# PWR.net
KiCad netlist of a schematic drawn in Altium Designer
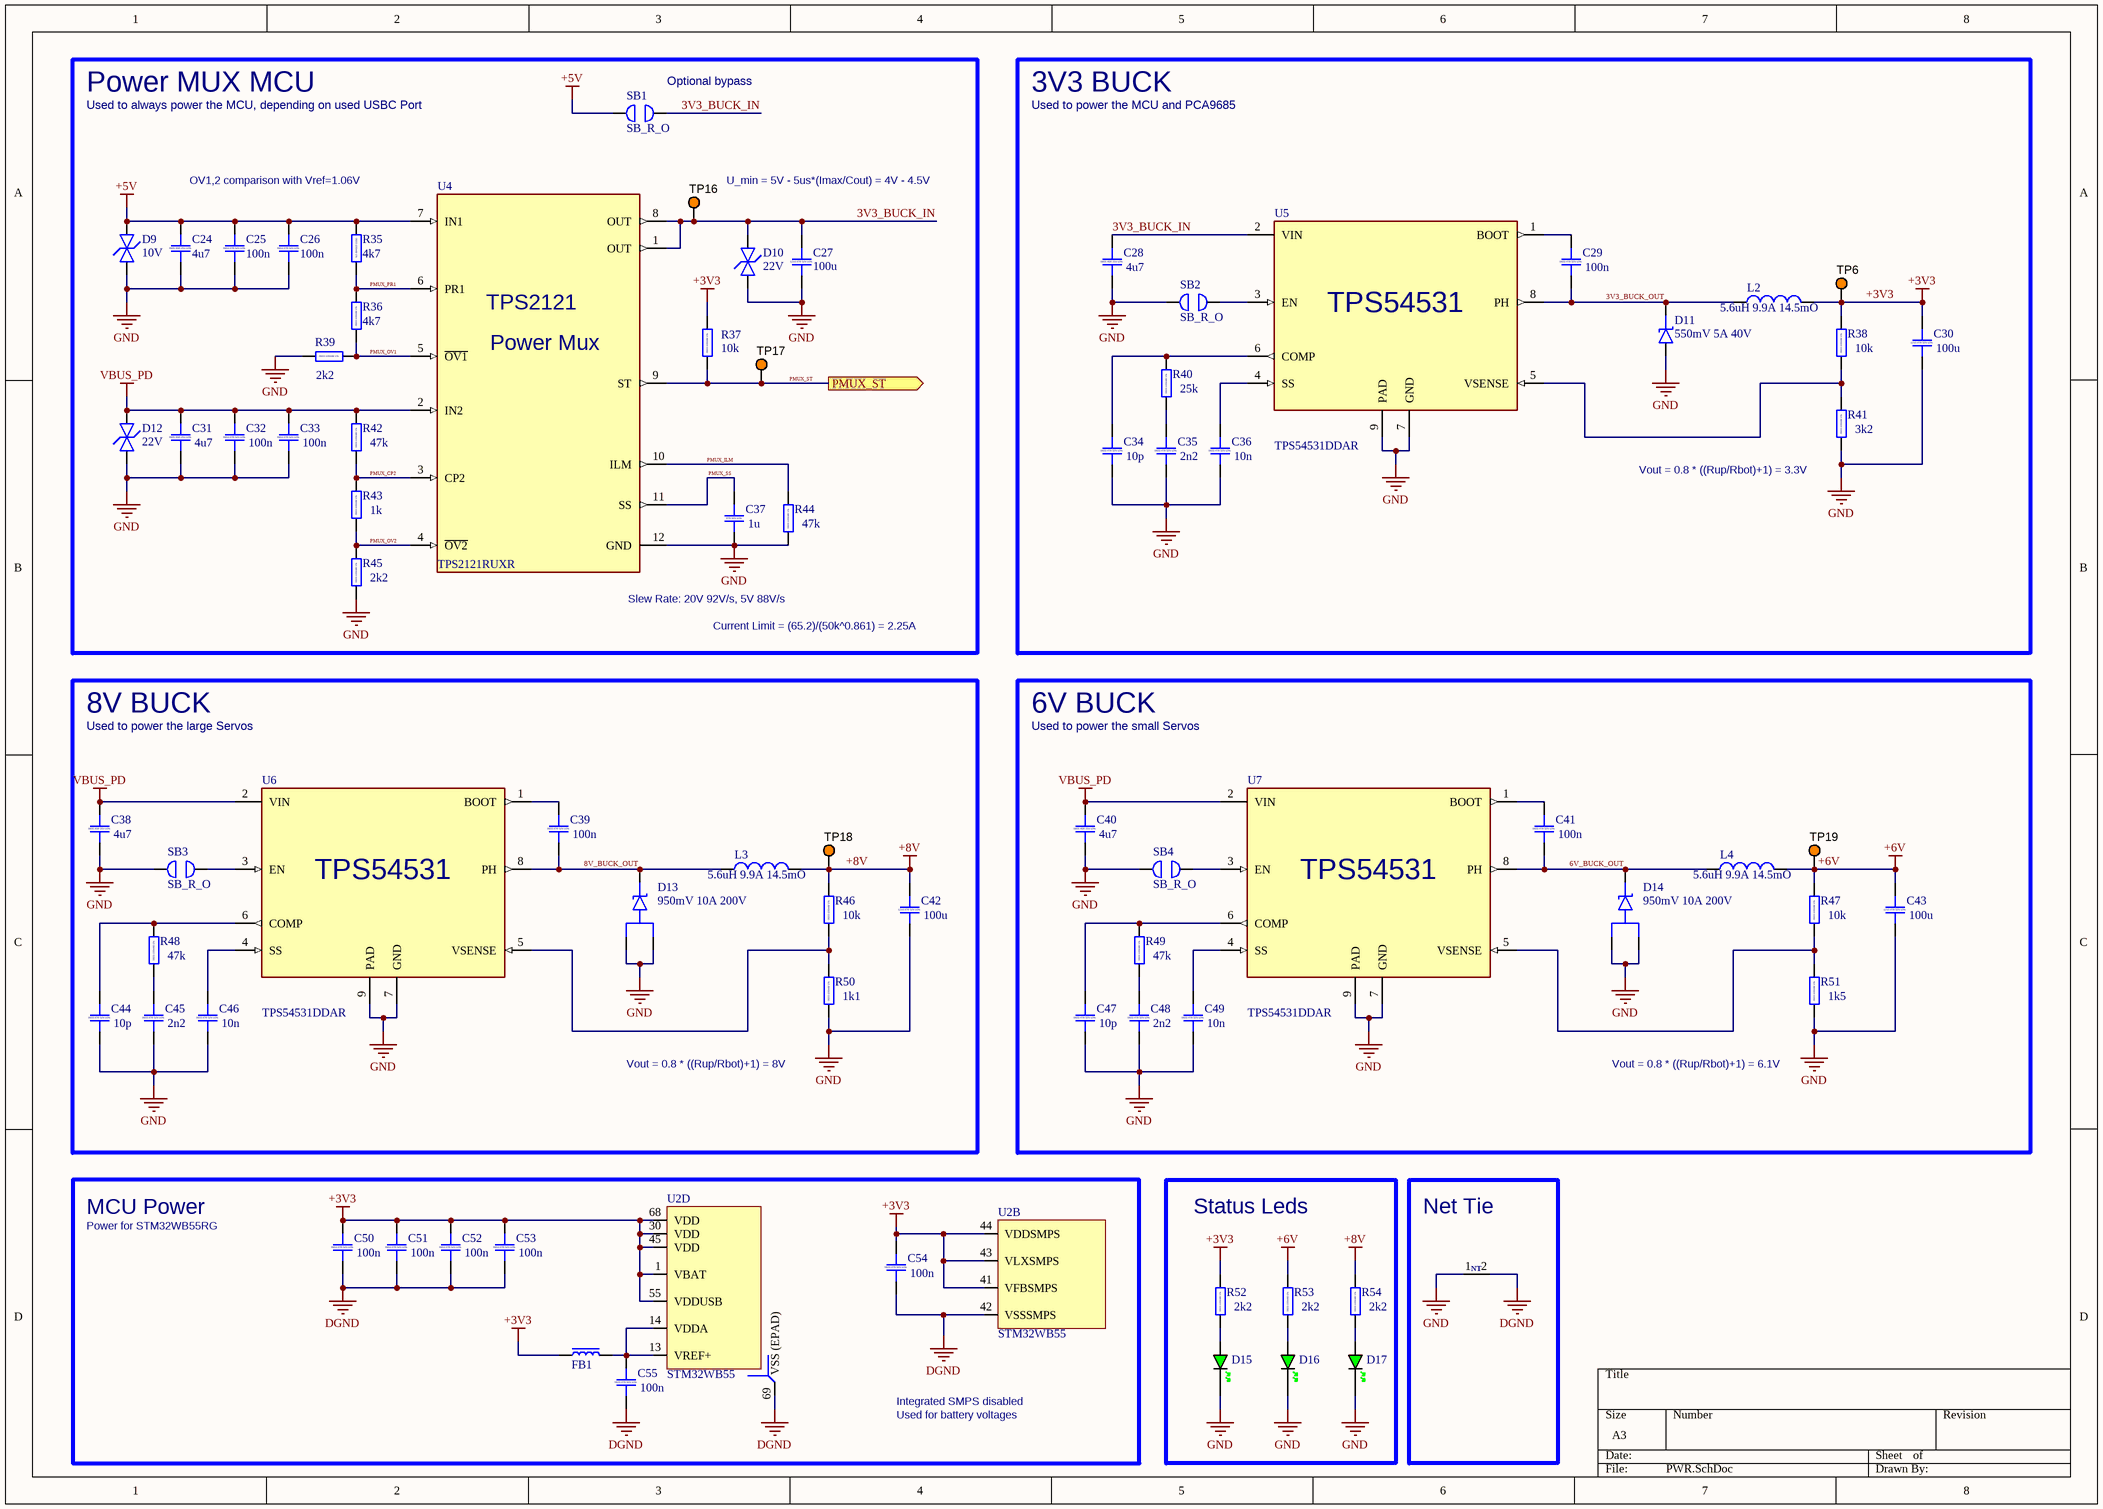
[diagram p0: PWR.SchDoc]

(export (version "E")
  (design (tool "Eeschema 10.0.6"))
  (components
    (comp (ref "C24")
      (value "4u7")
      (footprint "CAP_0805")
      (description "Capacitor SMD 0805")
      (fields (field (name "SOURCE") "Schematic-Lib-PhilsLab.SchLib"))
      (libsource (lib "") (part "CAP_EL_NP_5MM_2"))
    )
    (comp (ref "C25")
      (value "100n")
      (footprint "CAP_0603")
      (description "Capacitor SMD 0603")
      (fields (field (name "SOURCE") "Schematic-Lib-PhilsLab.SchLib"))
      (libsource (lib "Leonhard Waibl") (part "CAP_EL_NP_5MM"))
    )
    (comp (ref "C26")
      (value "100n")
      (footprint "CAP_0603")
      (description "Capacitor SMD 0603")
      (fields (field (name "SOURCE") "Schematic-Lib-PhilsLab.SchLib"))
      (libsource (lib "Leonhard Waibl") (part "CAP_EL_NP_5MM"))
    )
    (comp (ref "C27")
      (value "100u")
      (footprint "CAP_1210")
      (description "Capacitor SMD 1210")
      (fields (field (name "SOURCE") "Schematic-Lib-PhilsLab.SchLib"))
      (libsource (lib "") (part "CAP_EL_NP_5MM_1"))
    )
    (comp (ref "C28")
      (value "4u7")
      (footprint "CAP_0805")
      (description "Capacitor SMD 0805")
      (fields (field (name "SOURCE") "Schematic-Lib-PhilsLab.SchLib"))
      (libsource (lib "") (part "CAP_EL_NP_5MM_2"))
    )
    (comp (ref "C29")
      (value "100n")
      (footprint "CAP_0603")
      (description "Capacitor SMD 0603")
      (fields (field (name "SOURCE") "Schematic-Lib-PhilsLab.SchLib"))
      (libsource (lib "Leonhard Waibl") (part "CAP_EL_NP_5MM"))
    )
    (comp (ref "C30")
      (value "100u")
      (footprint "CAP_1210")
      (description "Capacitor SMD 1210")
      (fields (field (name "SOURCE") "Schematic-Lib-PhilsLab.SchLib"))
      (libsource (lib "") (part "CAP_EL_NP_5MM_1"))
    )
    (comp (ref "C31")
      (value "4u7")
      (footprint "CAP_0805")
      (description "Capacitor SMD 0805")
      (fields (field (name "SOURCE") "Schematic-Lib-PhilsLab.SchLib"))
      (libsource (lib "") (part "CAP_EL_NP_5MM_2"))
    )
    (comp (ref "C32")
      (value "100n")
      (footprint "CAP_0603")
      (description "Capacitor SMD 0603")
      (fields (field (name "SOURCE") "Schematic-Lib-PhilsLab.SchLib"))
      (libsource (lib "Leonhard Waibl") (part "CAP_EL_NP_5MM"))
    )
    (comp (ref "C33")
      (value "100n")
      (footprint "CAP_0603")
      (description "Capacitor SMD 0603")
      (fields (field (name "SOURCE") "Schematic-Lib-PhilsLab.SchLib"))
      (libsource (lib "Leonhard Waibl") (part "CAP_EL_NP_5MM"))
    )
    (comp (ref "C34")
      (value "10p")
      (footprint "CAP_0603")
      (description "Capacitor SMD 0603")
      (fields (field (name "SOURCE") "Schematic-Lib-PhilsLab.SchLib"))
      (libsource (lib "Leonhard Waibl") (part "CAP_EL_NP_5MM"))
    )
    (comp (ref "C35")
      (value "2n2")
      (footprint "CAP_0603")
      (description "Capacitor SMD 0603")
      (fields (field (name "SOURCE") "Schematic-Lib-PhilsLab.SchLib"))
      (libsource (lib "Leonhard Waibl") (part "CAP_EL_NP_5MM"))
    )
    (comp (ref "C36")
      (value "10n")
      (footprint "CAP_0603")
      (description "Capacitor SMD 0603")
      (fields (field (name "SOURCE") "Schematic-Lib-PhilsLab.SchLib"))
      (libsource (lib "Leonhard Waibl") (part "CAP_EL_NP_5MM"))
    )
    (comp (ref "C37")
      (value "1u")
      (footprint "CAP_0603")
      (description "Capacitor SMD 0603")
      (fields (field (name "SOURCE") "Schematic-Lib-PhilsLab.SchLib"))
      (libsource (lib "Leonhard Waibl") (part "CAP_EL_NP_5MM"))
    )
    (comp (ref "C38")
      (value "4u7")
      (footprint "CAP_0805")
      (description "Capacitor SMD 0805")
      (fields (field (name "SOURCE") "Schematic-Lib-PhilsLab.SchLib"))
      (libsource (lib "") (part "CAP_EL_NP_5MM_2"))
    )
    (comp (ref "C39")
      (value "100n")
      (footprint "CAP_0603")
      (description "Capacitor SMD 0603")
      (fields (field (name "SOURCE") "Schematic-Lib-PhilsLab.SchLib"))
      (libsource (lib "Leonhard Waibl") (part "CAP_EL_NP_5MM"))
    )
    (comp (ref "C40")
      (value "4u7")
      (footprint "CAP_0805")
      (description "Capacitor SMD 0805")
      (fields (field (name "SOURCE") "Schematic-Lib-PhilsLab.SchLib"))
      (libsource (lib "") (part "CAP_EL_NP_5MM_2"))
    )
    (comp (ref "C41")
      (value "100n")
      (footprint "CAP_0603")
      (description "Capacitor SMD 0603")
      (fields (field (name "SOURCE") "Schematic-Lib-PhilsLab.SchLib"))
      (libsource (lib "Leonhard Waibl") (part "CAP_EL_NP_5MM"))
    )
    (comp (ref "C42")
      (value "100u")
      (footprint "CAP_1210")
      (description "Capacitor SMD 1210")
      (fields (field (name "SOURCE") "Schematic-Lib-PhilsLab.SchLib"))
      (libsource (lib "") (part "CAP_EL_NP_5MM_1"))
    )
    (comp (ref "C43")
      (value "100u")
      (footprint "CAP_1210")
      (description "Capacitor SMD 1210")
      (fields (field (name "SOURCE") "Schematic-Lib-PhilsLab.SchLib"))
      (libsource (lib "") (part "CAP_EL_NP_5MM_1"))
    )
    (comp (ref "C44")
      (value "10p")
      (footprint "CAP_0603")
      (description "Capacitor SMD 0603")
      (fields (field (name "SOURCE") "Schematic-Lib-PhilsLab.SchLib"))
      (libsource (lib "Leonhard Waibl") (part "CAP_EL_NP_5MM"))
    )
    (comp (ref "C45")
      (value "2n2")
      (footprint "CAP_0603")
      (description "Capacitor SMD 0603")
      (fields (field (name "SOURCE") "Schematic-Lib-PhilsLab.SchLib"))
      (libsource (lib "Leonhard Waibl") (part "CAP_EL_NP_5MM"))
    )
    (comp (ref "C46")
      (value "10n")
      (footprint "CAP_0603")
      (description "Capacitor SMD 0603")
      (fields (field (name "SOURCE") "Schematic-Lib-PhilsLab.SchLib"))
      (libsource (lib "Leonhard Waibl") (part "CAP_EL_NP_5MM"))
    )
    (comp (ref "C47")
      (value "10p")
      (footprint "CAP_0603")
      (description "Capacitor SMD 0603")
      (fields (field (name "SOURCE") "Schematic-Lib-PhilsLab.SchLib"))
      (libsource (lib "Leonhard Waibl") (part "CAP_EL_NP_5MM"))
    )
    (comp (ref "C48")
      (value "2n2")
      (footprint "CAP_0603")
      (description "Capacitor SMD 0603")
      (fields (field (name "SOURCE") "Schematic-Lib-PhilsLab.SchLib"))
      (libsource (lib "Leonhard Waibl") (part "CAP_EL_NP_5MM"))
    )
    (comp (ref "C49")
      (value "10n")
      (footprint "CAP_0603")
      (description "Capacitor SMD 0603")
      (fields (field (name "SOURCE") "Schematic-Lib-PhilsLab.SchLib"))
      (libsource (lib "Leonhard Waibl") (part "CAP_EL_NP_5MM"))
    )
    (comp (ref "C50")
      (value "100n")
      (footprint "CAP_0603")
      (description "Capacitor SMD 0603")
      (fields (field (name "SOURCE") "Schematic-Lib-PhilsLab.SchLib"))
      (libsource (lib "Leonhard Waibl") (part "CAP_EL_NP_5MM"))
    )
    (comp (ref "C51")
      (value "100n")
      (footprint "CAP_0603")
      (description "Capacitor SMD 0603")
      (fields (field (name "SOURCE") "Schematic-Lib-PhilsLab.SchLib"))
      (libsource (lib "Leonhard Waibl") (part "CAP_EL_NP_5MM"))
    )
    (comp (ref "C52")
      (value "100n")
      (footprint "CAP_0603")
      (description "Capacitor SMD 0603")
      (fields (field (name "SOURCE") "Schematic-Lib-PhilsLab.SchLib"))
      (libsource (lib "Leonhard Waibl") (part "CAP_EL_NP_5MM"))
    )
    (comp (ref "C53")
      (value "100n")
      (footprint "CAP_0603")
      (description "Capacitor SMD 0603")
      (fields (field (name "SOURCE") "Schematic-Lib-PhilsLab.SchLib"))
      (libsource (lib "Leonhard Waibl") (part "CAP_EL_NP_5MM"))
    )
    (comp (ref "C54")
      (value "100n")
      (footprint "CAP_0603")
      (description "Capacitor SMD 0603")
      (fields (field (name "SOURCE") "Schematic-Lib-PhilsLab.SchLib"))
      (libsource (lib "Leonhard Waibl") (part "CAP_EL_NP_5MM"))
    )
    (comp (ref "C55")
      (value "100n")
      (footprint "CAP_0603")
      (description "Capacitor SMD 0603")
      (fields (field (name "SOURCE") "Schematic-Lib-PhilsLab.SchLib"))
      (libsource (lib "Leonhard Waibl") (part "CAP_EL_NP_5MM"))
    )
    (comp (ref "D9")
      (value "10V")
      (footprint "D_0603")
      (description "Diode TVS / ESD Bidirectional 0603")
      (fields (field (name "SOURCE") "Schematic-Lib-PhilsLab.SchLib"))
      (libsource (lib "Leonhard Waibl") (part "D_TVS_BI_0603"))
    )
    (comp (ref "D10")
      (value "22V")
      (footprint "D_0603")
      (description "Diode TVS / ESD Bidirectional 0603")
      (fields (field (name "SOURCE") "Schematic-Lib-PhilsLab.SchLib"))
      (libsource (lib "Leonhard Waibl") (part "D_TVS_BI_0603"))
    )
    (comp (ref "D11")
      (value "550mV 5A 40V")
      (footprint "SMC-DO-214AB")
      (description "Diode Schottky SMD SMC (DO-214AB)")
      (fields (field (name "SOURCE") "Schematic-Lib-PhilsLab.SchLib"))
      (libsource (lib "Leonhard Waibl") (part "D_SCHOTTKY_SOD_323"))
    )
    (comp (ref "D12")
      (value "22V")
      (footprint "D_0603")
      (description "Diode TVS / ESD Bidirectional 0603")
      (fields (field (name "SOURCE") "Schematic-Lib-PhilsLab.SchLib"))
      (libsource (lib "Leonhard Waibl") (part "D_TVS_BI_0603"))
    )
    (comp (ref "D13")
      (value "950mV 10A 200V")
      (footprint "DPAK230P970X240-3N")
      (description "Diode Schottky DPAK")
      (fields (field (name "SOURCE") "Schematic-Lib-PhilsLab.SchLib"))
      (libsource (lib "") (part "D_SCHOTTKY_SOD_323_1"))
    )
    (comp (ref "D14")
      (value "950mV 10A 200V")
      (footprint "DPAK230P970X240-3N")
      (description "Diode Schottky DPAK")
      (fields (field (name "SOURCE") "Schematic-Lib-PhilsLab.SchLib"))
      (libsource (lib "") (part "D_SCHOTTKY_SOD_323_1"))
    )
    (comp (ref "D15")
      (value "LED_0603_GREEN")
      (footprint "LED_0603_GREEN")
      (description "LED 0603 GREEN SMD")
      (fields (field (name "SOURCE") "Schematic-Lib-PhilsLab.SchLib"))
      (libsource (lib "Leonhard Waibl") (part "LED_0805_GREEN"))
    )
    (comp (ref "D16")
      (value "LED_0603_GREEN")
      (footprint "LED_0603_GREEN")
      (description "LED 0603 GREEN SMD")
      (fields (field (name "SOURCE") "Schematic-Lib-PhilsLab.SchLib"))
      (libsource (lib "Leonhard Waibl") (part "LED_0805_GREEN"))
    )
    (comp (ref "D17")
      (value "LED_0603_GREEN")
      (footprint "LED_0603_GREEN")
      (description "LED 0603 GREEN SMD")
      (fields (field (name "SOURCE") "Schematic-Lib-PhilsLab.SchLib"))
      (libsource (lib "Leonhard Waibl") (part "LED_0805_GREEN"))
    )
    (comp (ref "FB1")
      (value "FB_0603")
      (footprint "FB_0603")
      (description "Ferrite Bead SMD 0603")
      (fields (field (name "SOURCE") "Schematic-Lib-PhilsLab.SchLib"))
      (libsource (lib "Leonhard Waibl") (part "FB_0805"))
    )
    (comp (ref "L2")
      (value "5.6uH 9.9A 14.5mO")
      (footprint "INDP6466X61N")
      (fields (field (name "TOLERANCE") "20%"))
      (libsource (lib "Leonhard Waibl") (part "IND-2"))
    )
    (comp (ref "L3")
      (value "5.6uH 9.9A 14.5mO")
      (footprint "INDP6466X61N")
      (fields (field (name "TOLERANCE") "20%"))
      (libsource (lib "Leonhard Waibl") (part "IND-2"))
    )
    (comp (ref "L4")
      (value "5.6uH 9.9A 14.5mO")
      (footprint "INDP6466X61N")
      (fields (field (name "TOLERANCE") "20%"))
      (libsource (lib "Leonhard Waibl") (part "IND-2"))
    )
    (comp (ref "NT1")
      (value "NetTie_1mm")
      (footprint "NETTIE")
      (description "Net Tie")
      (fields (field (name "SOURCE") "Schematic-Lib-PhilsLab.SchLib"))
      (libsource (lib "Leonhard Waibl") (part "NetTie"))
    )
    (comp (ref "R35")
      (value "4k7")
      (footprint "RES_0603")
      (description "Resistor 0603 100mW 1%")
      (fields (field (name "SOURCE") "Schematic-Lib-PhilsLab.SchLib"))
      (libsource (lib "Leonhard Waibl") (part "RES_5931"))
    )
    (comp (ref "R36")
      (value "4k7")
      (footprint "RES_0603")
      (description "Resistor 0603 100mW 1%")
      (fields (field (name "SOURCE") "Schematic-Lib-PhilsLab.SchLib"))
      (libsource (lib "Leonhard Waibl") (part "RES_5931"))
    )
    (comp (ref "R37")
      (value "10k")
      (footprint "RES_0603")
      (description "Resistor 0603 100mW 1%")
      (fields (field (name "SOURCE") "Schematic-Lib-PhilsLab.SchLib"))
      (libsource (lib "Leonhard Waibl") (part "RES_5931"))
    )
    (comp (ref "R38")
      (value "10k")
      (footprint "RES_0603")
      (description "Resistor 0603 100mW 1%")
      (fields (field (name "SOURCE") "Schematic-Lib-PhilsLab.SchLib"))
      (libsource (lib "Leonhard Waibl") (part "RES_5931"))
    )
    (comp (ref "R39")
      (value "2k2")
      (footprint "RES_0603")
      (description "Resistor 0603 100mW 1%")
      (fields (field (name "SOURCE") "Schematic-Lib-PhilsLab.SchLib"))
      (libsource (lib "Leonhard Waibl") (part "RES_5931"))
    )
    (comp (ref "R40")
      (value "25k")
      (footprint "RES_0603")
      (description "Resistor 0603 100mW 1%")
      (fields (field (name "SOURCE") "Schematic-Lib-PhilsLab.SchLib"))
      (libsource (lib "Leonhard Waibl") (part "RES_5931"))
    )
    (comp (ref "R41")
      (value "3k2")
      (footprint "RES_0603")
      (description "Resistor 0603 100mW 1%")
      (fields (field (name "SOURCE") "Schematic-Lib-PhilsLab.SchLib"))
      (libsource (lib "Leonhard Waibl") (part "RES_5931"))
    )
    (comp (ref "R42")
      (value "47k")
      (footprint "RES_0603")
      (description "Resistor 0603 100mW 1%")
      (fields (field (name "SOURCE") "Schematic-Lib-PhilsLab.SchLib"))
      (libsource (lib "Leonhard Waibl") (part "RES_5931"))
    )
    (comp (ref "R43")
      (value "1k")
      (footprint "RES_0603")
      (description "Resistor 0603 100mW 1%")
      (fields (field (name "SOURCE") "Schematic-Lib-PhilsLab.SchLib"))
      (libsource (lib "Leonhard Waibl") (part "RES_5931"))
    )
    (comp (ref "R44")
      (value "47k")
      (footprint "RES_0603")
      (description "Resistor 0603 100mW 1%")
      (fields (field (name "SOURCE") "Schematic-Lib-PhilsLab.SchLib"))
      (libsource (lib "Leonhard Waibl") (part "RES_5931"))
    )
    (comp (ref "R45")
      (value "2k2")
      (footprint "RES_0603")
      (description "Resistor 0603 100mW 1%")
      (fields (field (name "SOURCE") "Schematic-Lib-PhilsLab.SchLib"))
      (libsource (lib "Leonhard Waibl") (part "RES_5931"))
    )
    (comp (ref "R46")
      (value "10k")
      (footprint "RES_0603")
      (description "Resistor 0603 100mW 1%")
      (fields (field (name "SOURCE") "Schematic-Lib-PhilsLab.SchLib"))
      (libsource (lib "Leonhard Waibl") (part "RES_5931"))
    )
    (comp (ref "R47")
      (value "10k")
      (footprint "RES_0603")
      (description "Resistor 0603 100mW 1%")
      (fields (field (name "SOURCE") "Schematic-Lib-PhilsLab.SchLib"))
      (libsource (lib "Leonhard Waibl") (part "RES_5931"))
    )
    (comp (ref "R48")
      (value "47k")
      (footprint "RES_0603")
      (description "Resistor 0603 100mW 1%")
      (fields (field (name "SOURCE") "Schematic-Lib-PhilsLab.SchLib"))
      (libsource (lib "Leonhard Waibl") (part "RES_5931"))
    )
    (comp (ref "R49")
      (value "47k")
      (footprint "RES_0603")
      (description "Resistor 0603 100mW 1%")
      (fields (field (name "SOURCE") "Schematic-Lib-PhilsLab.SchLib"))
      (libsource (lib "Leonhard Waibl") (part "RES_5931"))
    )
    (comp (ref "R50")
      (value "1k1")
      (footprint "RES_0603")
      (description "Resistor 0603 100mW 1%")
      (fields (field (name "SOURCE") "Schematic-Lib-PhilsLab.SchLib"))
      (libsource (lib "Leonhard Waibl") (part "RES_5931"))
    )
    (comp (ref "R51")
      (value "1k5")
      (footprint "RES_0603")
      (description "Resistor 0603 100mW 1%")
      (fields (field (name "SOURCE") "Schematic-Lib-PhilsLab.SchLib"))
      (libsource (lib "Leonhard Waibl") (part "RES_5931"))
    )
    (comp (ref "R52")
      (value "2k2")
      (footprint "RES_0603")
      (description "Resistor 0603 100mW 1%")
      (fields (field (name "SOURCE") "Schematic-Lib-PhilsLab.SchLib"))
      (libsource (lib "Leonhard Waibl") (part "RES_5931"))
    )
    (comp (ref "R53")
      (value "2k2")
      (footprint "RES_0603")
      (description "Resistor 0603 100mW 1%")
      (fields (field (name "SOURCE") "Schematic-Lib-PhilsLab.SchLib"))
      (libsource (lib "Leonhard Waibl") (part "RES_5931"))
    )
    (comp (ref "R54")
      (value "2k2")
      (footprint "RES_0603")
      (description "Resistor 0603 100mW 1%")
      (fields (field (name "SOURCE") "Schematic-Lib-PhilsLab.SchLib"))
      (libsource (lib "Leonhard Waibl") (part "RES_5931"))
    )
    (comp (ref "SB1")
      (value "SB_R_O")
      (footprint "New footprint 1")
      (description "Solderbridge Round and Open")
      (libsource (lib "Leonhard Waibl") (part "SB_Open"))
    )
    (comp (ref "SB2")
      (value "SB_R_O")
      (footprint "New footprint 1")
      (description "Solderbridge Round and Open")
      (libsource (lib "Leonhard Waibl") (part "SB_Open"))
    )
    (comp (ref "SB3")
      (value "SB_R_O")
      (footprint "New footprint 1")
      (description "Solderbridge Round and Open")
      (libsource (lib "Leonhard Waibl") (part "SB_Open"))
    )
    (comp (ref "SB4")
      (value "SB_R_O")
      (footprint "New footprint 1")
      (description "Solderbridge Round and Open")
      (libsource (lib "Leonhard Waibl") (part "SB_Open"))
    )
    (comp (ref "TP6")
      (value "5003")
      (footprint "KSTN-5003")
      (description "Test Point, Orange, Height 4.6 mm, Tail Length 3 mm, 1-Pin THD, RoHS")
      (fields (field (name "MANUFACTURER") "Keystone"))
      (libsource (lib "Leonhard Waibl") (part "TESTPOINT_ORANGE"))
    )
    (comp (ref "TP16")
      (value "5003")
      (footprint "KSTN-5003")
      (description "Test Point, Orange, Height 4.6 mm, Tail Length 3 mm, 1-Pin THD, RoHS")
      (fields (field (name "MANUFACTURER") "Keystone"))
      (libsource (lib "Leonhard Waibl") (part "TESTPOINT_ORANGE"))
    )
    (comp (ref "TP17")
      (value "5003")
      (footprint "KSTN-5003")
      (description "Test Point, Orange, Height 4.6 mm, Tail Length 3 mm, 1-Pin THD, RoHS")
      (fields (field (name "MANUFACTURER") "Keystone"))
      (libsource (lib "Leonhard Waibl") (part "TESTPOINT_ORANGE"))
    )
    (comp (ref "TP18")
      (value "5003")
      (footprint "KSTN-5003")
      (description "Test Point, Orange, Height 4.6 mm, Tail Length 3 mm, 1-Pin THD, RoHS")
      (fields (field (name "MANUFACTURER") "Keystone"))
      (libsource (lib "Leonhard Waibl") (part "TESTPOINT_ORANGE"))
    )
    (comp (ref "TP19")
      (value "5003")
      (footprint "KSTN-5003")
      (description "Test Point, Orange, Height 4.6 mm, Tail Length 3 mm, 1-Pin THD, RoHS")
      (fields (field (name "MANUFACTURER") "Keystone"))
      (libsource (lib "Leonhard Waibl") (part "TESTPOINT_ORANGE"))
    )
    (comp (ref "U2")
      (value "STM32WB55")
      (footprint "QFN40P800X800X100_HS-69N")
      (description "Multiprotocol wireless 32-bit MCU Arm®-based Cortex®-M4")
      (libsource (lib "Leonhard Waibl") (part "STM32WBxx_QFN68"))
    )
    (comp (ref "U4")
      (value "TPS2121RUXR")
      (footprint "FP-RUX0012A-MFG")
      (description "Power Supply Support Circuit, Adjustable, 1 Channel, PQCC12")
      (libsource (lib "Leonhard Waibl") (part "7e2eec2e55e3eba557c36dfb5d176d9"))
    )
    (comp (ref "U5")
      (value "TPS54531DDAR")
      (footprint "FP-DDA0008E-IPC_A")
      (description "Switching Regulator, Current-mode, 5A, 570kHz Switching Freq-Max, PDSO8")
      (libsource (lib "Leonhard Waibl") (part "0ba9c67d8848e7a3c062535a516a02c"))
    )
    (comp (ref "U6")
      (value "TPS54531DDAR")
      (footprint "FP-DDA0008E-IPC_A")
      (description "Switching Regulator, Current-mode, 5A, 570kHz Switching Freq-Max, PDSO8")
      (libsource (lib "Leonhard Waibl") (part "0ba9c67d8848e7a3c062535a516a02c"))
    )
    (comp (ref "U7")
      (value "TPS54531DDAR")
      (footprint "FP-DDA0008E-IPC_A")
      (description "Switching Regulator, Current-mode, 5A, 570kHz Switching Freq-Max, PDSO8")
      (libsource (lib "Leonhard Waibl") (part "0ba9c67d8848e7a3c062535a516a02c"))
    )
  )
  (nets
    (net (code "1") (name "+3V3") (class "Default")
      (node (ref "C30") (pin "2") (pinfunction "2_2") (pintype "passive"))
      (node (ref "C50") (pin "1") (pinfunction "1_1") (pintype "passive"))
      (node (ref "C51") (pin "1") (pinfunction "1_1") (pintype "passive"))
      (node (ref "C52") (pin "1") (pinfunction "1_1") (pintype "passive"))
      (node (ref "C53") (pin "1") (pinfunction "1_1") (pintype "passive"))
      (node (ref "C54") (pin "1") (pinfunction "1_1") (pintype "passive"))
      (node (ref "FB1") (pin "1") (pinfunction "1_1") (pintype "passive"))
      (node (ref "L2") (pin "2") (pinfunction "2_2") (pintype "passive"))
      (node (ref "R37") (pin "2") (pinfunction "2_2") (pintype "passive"))
      (node (ref "R38") (pin "2") (pinfunction "2_2") (pintype "passive"))
      (node (ref "R52") (pin "2") (pinfunction "2_2") (pintype "passive"))
      (node (ref "TP6") (pin "1") (pinfunction "1_1") (pintype "passive"))
      (node (ref "U2") (pin "1") (pinfunction "VBAT_1") (pintype "passive"))
      (node (ref "U2") (pin "30") (pinfunction "VDD_30") (pintype "passive"))
      (node (ref "U2") (pin "41") (pinfunction "VFBSMPS_41") (pintype "passive"))
      (node (ref "U2") (pin "43") (pinfunction "VLXSMPS_43") (pintype "passive"))
      (node (ref "U2") (pin "44") (pinfunction "VDDSMPS_44") (pintype "passive"))
      (node (ref "U2") (pin "45") (pinfunction "VDD_45") (pintype "passive"))
      (node (ref "U2") (pin "55") (pinfunction "VDDUSB_55") (pintype "passive"))
      (node (ref "U2") (pin "68") (pinfunction "VDD_68") (pintype "passive"))
    )
    (net (code "2") (name "+5V") (class "Default")
      (node (ref "C24") (pin "2") (pinfunction "2_2") (pintype "passive"))
      (node (ref "C25") (pin "1") (pinfunction "1_1") (pintype "passive"))
      (node (ref "C26") (pin "1") (pinfunction "1_1") (pintype "passive"))
      (node (ref "D9") (pin "K") (pinfunction "K_K") (pintype "passive"))
      (node (ref "R35") (pin "1") (pinfunction "1_1") (pintype "passive"))
      (node (ref "SB1") (pin "1") (pinfunction "1_1") (pintype "passive"))
      (node (ref "U4") (pin "7") (pinfunction "IN1_7") (pintype "input"))
    )
    (net (code "3") (name "+6V") (class "Default")
      (node (ref "C43") (pin "2") (pinfunction "2_2") (pintype "passive"))
      (node (ref "L4") (pin "2") (pinfunction "2_2") (pintype "passive"))
      (node (ref "R47") (pin "2") (pinfunction "2_2") (pintype "passive"))
      (node (ref "R53") (pin "2") (pinfunction "2_2") (pintype "passive"))
      (node (ref "TP19") (pin "1") (pinfunction "1_1") (pintype "passive"))
    )
    (net (code "4") (name "+8V") (class "Default")
      (node (ref "C42") (pin "2") (pinfunction "2_2") (pintype "passive"))
      (node (ref "L3") (pin "2") (pinfunction "2_2") (pintype "passive"))
      (node (ref "R46") (pin "2") (pinfunction "2_2") (pintype "passive"))
      (node (ref "R54") (pin "2") (pinfunction "2_2") (pintype "passive"))
      (node (ref "TP18") (pin "1") (pinfunction "1_1") (pintype "passive"))
    )
    (net (code "5") (name "/3V3_BUCK_IN") (class "Default")
      (node (ref "C27") (pin "2") (pinfunction "2_2") (pintype "passive"))
      (node (ref "C28") (pin "2") (pinfunction "2_2") (pintype "passive"))
      (node (ref "D10") (pin "K") (pinfunction "K_K") (pintype "passive"))
      (node (ref "SB1") (pin "2") (pinfunction "2_2") (pintype "passive"))
      (node (ref "TP16") (pin "1") (pinfunction "1_1") (pintype "passive"))
      (node (ref "U4") (pin "1") (pinfunction "OUT_1") (pintype "output"))
      (node (ref "U4") (pin "8") (pinfunction "OUT_8") (pintype "output"))
      (node (ref "U5") (pin "2") (pinfunction "VIN_2") (pintype "power_in"))
    )
    (net (code "6") (name "/3V3_BUCK_OUT") (class "Default")
      (node (ref "C29") (pin "2") (pinfunction "2_2") (pintype "passive"))
      (node (ref "D11") (pin "K") (pinfunction "K_K") (pintype "passive"))
      (node (ref "L2") (pin "1") (pinfunction "1_1") (pintype "passive"))
      (node (ref "U5") (pin "8") (pinfunction "PH_8") (pintype "output"))
    )
    (net (code "7") (name "/6V_BUCK_OUT") (class "Default")
      (node (ref "C41") (pin "2") (pinfunction "2_2") (pintype "passive"))
      (node (ref "D14") (pin "3") (pinfunction "K_3") (pintype "passive"))
      (node (ref "L4") (pin "1") (pinfunction "1_1") (pintype "passive"))
      (node (ref "U7") (pin "8") (pinfunction "PH_8") (pintype "output"))
    )
    (net (code "8") (name "/8V_BUCK_OUT") (class "Default")
      (node (ref "C39") (pin "2") (pinfunction "2_2") (pintype "passive"))
      (node (ref "D13") (pin "3") (pinfunction "K_3") (pintype "passive"))
      (node (ref "L3") (pin "1") (pinfunction "1_1") (pintype "passive"))
      (node (ref "U6") (pin "8") (pinfunction "PH_8") (pintype "output"))
    )
    (net (code "9") (name "/PMUX_CP2") (class "Default")
      (node (ref "R42") (pin "1") (pinfunction "1_1") (pintype "passive"))
      (node (ref "R43") (pin "2") (pinfunction "2_2") (pintype "passive"))
      (node (ref "U4") (pin "3") (pinfunction "CP2_3") (pintype "input"))
    )
    (net (code "10") (name "/PMUX_ILM") (class "Default")
      (node (ref "R44") (pin "2") (pinfunction "2_2") (pintype "passive"))
      (node (ref "U4") (pin "10") (pinfunction "ILM_10") (pintype "output"))
    )
    (net (code "11") (name "/PMUX_OV1") (class "Default")
      (node (ref "R36") (pin "1") (pinfunction "1_1") (pintype "passive"))
      (node (ref "R39") (pin "2") (pinfunction "2_2") (pintype "passive"))
      (node (ref "U4") (pin "5") (pinfunction "~{OV1}_5") (pintype "input"))
    )
    (net (code "12") (name "/PMUX_OV2") (class "Default")
      (node (ref "R43") (pin "1") (pinfunction "1_1") (pintype "passive"))
      (node (ref "R45") (pin "2") (pinfunction "2_2") (pintype "passive"))
      (node (ref "U4") (pin "4") (pinfunction "~{OV2}_4") (pintype "input"))
    )
    (net (code "13") (name "/PMUX_PR1") (class "Default")
      (node (ref "R35") (pin "2") (pinfunction "2_2") (pintype "passive"))
      (node (ref "R36") (pin "2") (pinfunction "2_2") (pintype "passive"))
      (node (ref "U4") (pin "6") (pinfunction "PR1_6") (pintype "input"))
    )
    (net (code "14") (name "/PMUX_SS") (class "Default")
      (node (ref "C37") (pin "1") (pinfunction "1_1") (pintype "passive"))
      (node (ref "U4") (pin "11") (pinfunction "SS_11") (pintype "output"))
    )
    (net (code "15") (name "/PMUX_ST") (class "Default")
      (node (ref "R37") (pin "1") (pinfunction "1_1") (pintype "passive"))
      (node (ref "TP17") (pin "1") (pinfunction "1_1") (pintype "passive"))
      (node (ref "U4") (pin "9") (pinfunction "ST_9") (pintype "output"))
    )
    (net (code "16") (name "DGND") (class "Default")
      (node (ref "C50") (pin "2") (pinfunction "2_2") (pintype "passive"))
      (node (ref "C51") (pin "2") (pinfunction "2_2") (pintype "passive"))
      (node (ref "C52") (pin "2") (pinfunction "2_2") (pintype "passive"))
      (node (ref "C53") (pin "2") (pinfunction "2_2") (pintype "passive"))
      (node (ref "C54") (pin "2") (pinfunction "2_2") (pintype "passive"))
      (node (ref "C55") (pin "2") (pinfunction "2_2") (pintype "passive"))
      (node (ref "NT1") (pin "2") (pinfunction "2_2") (pintype "passive"))
      (node (ref "U2") (pin "42") (pinfunction "VSSSMPS_42") (pintype "passive"))
      (node (ref "U2") (pin "69") (pinfunction "VSS_(EPAD)_69") (pintype "passive"))
    )
    (net (code "17") (name "GND") (class "Default")
      (node (ref "C24") (pin "1") (pinfunction "1_1") (pintype "passive"))
      (node (ref "C25") (pin "2") (pinfunction "2_2") (pintype "passive"))
      (node (ref "C26") (pin "2") (pinfunction "2_2") (pintype "passive"))
      (node (ref "C27") (pin "1") (pinfunction "1_1") (pintype "passive"))
      (node (ref "C28") (pin "1") (pinfunction "1_1") (pintype "passive"))
      (node (ref "C30") (pin "1") (pinfunction "1_1") (pintype "passive"))
      (node (ref "C31") (pin "1") (pinfunction "1_1") (pintype "passive"))
      (node (ref "C32") (pin "2") (pinfunction "2_2") (pintype "passive"))
      (node (ref "C33") (pin "2") (pinfunction "2_2") (pintype "passive"))
      (node (ref "C34") (pin "2") (pinfunction "2_2") (pintype "passive"))
      (node (ref "C35") (pin "2") (pinfunction "2_2") (pintype "passive"))
      (node (ref "C36") (pin "2") (pinfunction "2_2") (pintype "passive"))
      (node (ref "C37") (pin "2") (pinfunction "2_2") (pintype "passive"))
      (node (ref "C38") (pin "1") (pinfunction "1_1") (pintype "passive"))
      (node (ref "C40") (pin "1") (pinfunction "1_1") (pintype "passive"))
      (node (ref "C42") (pin "1") (pinfunction "1_1") (pintype "passive"))
      (node (ref "C43") (pin "1") (pinfunction "1_1") (pintype "passive"))
      (node (ref "C44") (pin "2") (pinfunction "2_2") (pintype "passive"))
      (node (ref "C45") (pin "2") (pinfunction "2_2") (pintype "passive"))
      (node (ref "C46") (pin "2") (pinfunction "2_2") (pintype "passive"))
      (node (ref "C47") (pin "2") (pinfunction "2_2") (pintype "passive"))
      (node (ref "C48") (pin "2") (pinfunction "2_2") (pintype "passive"))
      (node (ref "C49") (pin "2") (pinfunction "2_2") (pintype "passive"))
      (node (ref "D10") (pin "A") (pinfunction "A_A") (pintype "passive"))
      (node (ref "D11") (pin "A") (pinfunction "A_A") (pintype "passive"))
      (node (ref "D12") (pin "A") (pinfunction "A_A") (pintype "passive"))
      (node (ref "D13") (pin "1") (pinfunction "A_1") (pintype "passive"))
      (node (ref "D13") (pin "2") (pinfunction "A1_2") (pintype "passive"))
      (node (ref "D14") (pin "1") (pinfunction "A_1") (pintype "passive"))
      (node (ref "D14") (pin "2") (pinfunction "A1_2") (pintype "passive"))
      (node (ref "D15") (pin "K") (pinfunction "K_K") (pintype "passive"))
      (node (ref "D16") (pin "K") (pinfunction "K_K") (pintype "passive"))
      (node (ref "D17") (pin "K") (pinfunction "K_K") (pintype "passive"))
      (node (ref "D9") (pin "A") (pinfunction "A_A") (pintype "passive"))
      (node (ref "NT1") (pin "1") (pinfunction "1_1") (pintype "passive"))
      (node (ref "R39") (pin "1") (pinfunction "1_1") (pintype "passive"))
      (node (ref "R41") (pin "1") (pinfunction "1_1") (pintype "passive"))
      (node (ref "R44") (pin "1") (pinfunction "1_1") (pintype "passive"))
      (node (ref "R45") (pin "1") (pinfunction "1_1") (pintype "passive"))
      (node (ref "R50") (pin "1") (pinfunction "1_1") (pintype "passive"))
      (node (ref "R51") (pin "1") (pinfunction "1_1") (pintype "passive"))
      (node (ref "SB2") (pin "1") (pinfunction "1_1") (pintype "passive"))
      (node (ref "SB3") (pin "1") (pinfunction "1_1") (pintype "passive"))
      (node (ref "SB4") (pin "1") (pinfunction "1_1") (pintype "passive"))
      (node (ref "U4") (pin "12") (pinfunction "GND_12") (pintype "power_in"))
      (node (ref "U5") (pin "7") (pinfunction "GND_7") (pintype "power_in"))
      (node (ref "U5") (pin "9") (pinfunction "PAD_9") (pintype "power_in"))
      (node (ref "U6") (pin "7") (pinfunction "GND_7") (pintype "power_in"))
      (node (ref "U6") (pin "9") (pinfunction "PAD_9") (pintype "power_in"))
      (node (ref "U7") (pin "7") (pinfunction "GND_7") (pintype "power_in"))
      (node (ref "U7") (pin "9") (pinfunction "PAD_9") (pintype "power_in"))
    )
    (net (code "18") (name "Net-(C35-Pad1)") (class "Default")
      (node (ref "C35") (pin "1") (pinfunction "1_1") (pintype "passive"))
      (node (ref "R40") (pin "1") (pinfunction "1_1") (pintype "passive"))
    )
    (net (code "19") (name "Net-(C45-Pad1)") (class "Default")
      (node (ref "C45") (pin "1") (pinfunction "1_1") (pintype "passive"))
      (node (ref "R48") (pin "1") (pinfunction "1_1") (pintype "passive"))
    )
    (net (code "20") (name "Net-(C48-Pad1)") (class "Default")
      (node (ref "C48") (pin "1") (pinfunction "1_1") (pintype "passive"))
      (node (ref "R49") (pin "1") (pinfunction "1_1") (pintype "passive"))
    )
    (net (code "21") (name "Net-(D15-PadA)") (class "Default")
      (node (ref "D15") (pin "A") (pinfunction "A_A") (pintype "passive"))
      (node (ref "R52") (pin "1") (pinfunction "1_1") (pintype "passive"))
    )
    (net (code "22") (name "Net-(D16-PadA)") (class "Default")
      (node (ref "D16") (pin "A") (pinfunction "A_A") (pintype "passive"))
      (node (ref "R53") (pin "1") (pinfunction "1_1") (pintype "passive"))
    )
    (net (code "23") (name "Net-(D17-PadA)") (class "Default")
      (node (ref "D17") (pin "A") (pinfunction "A_A") (pintype "passive"))
      (node (ref "R54") (pin "1") (pinfunction "1_1") (pintype "passive"))
    )
    (net (code "24") (name "Net-(U2D-VDDA)") (class "Default")
      (node (ref "C55") (pin "1") (pinfunction "1_1") (pintype "passive"))
      (node (ref "FB1") (pin "2") (pinfunction "2_2") (pintype "passive"))
      (node (ref "U2") (pin "13") (pinfunction "VREF+_13") (pintype "passive"))
      (node (ref "U2") (pin "14") (pinfunction "VDDA_14") (pintype "passive"))
    )
    (net (code "25") (name "Net-(U5-BOOT)") (class "Default")
      (node (ref "C29") (pin "1") (pinfunction "1_1") (pintype "passive"))
      (node (ref "U5") (pin "1") (pinfunction "BOOT_1") (pintype "output"))
    )
    (net (code "26") (name "Net-(U5-COMP)") (class "Default")
      (node (ref "C34") (pin "1") (pinfunction "1_1") (pintype "passive"))
      (node (ref "R40") (pin "2") (pinfunction "2_2") (pintype "passive"))
      (node (ref "U5") (pin "6") (pinfunction "COMP_6") (pintype "output"))
    )
    (net (code "27") (name "Net-(U5-EN)") (class "Default")
      (node (ref "SB2") (pin "2") (pinfunction "2_2") (pintype "passive"))
      (node (ref "U5") (pin "3") (pinfunction "EN_3") (pintype "input"))
    )
    (net (code "28") (name "Net-(U5-SS)") (class "Default")
      (node (ref "C36") (pin "1") (pinfunction "1_1") (pintype "passive"))
      (node (ref "U5") (pin "4") (pinfunction "SS_4") (pintype "input"))
    )
    (net (code "29") (name "Net-(U5-VSENSE)") (class "Default")
      (node (ref "R38") (pin "1") (pinfunction "1_1") (pintype "passive"))
      (node (ref "R41") (pin "2") (pinfunction "2_2") (pintype "passive"))
      (node (ref "U5") (pin "5") (pinfunction "VSENSE_5") (pintype "input"))
    )
    (net (code "30") (name "Net-(U6-BOOT)") (class "Default")
      (node (ref "C39") (pin "1") (pinfunction "1_1") (pintype "passive"))
      (node (ref "U6") (pin "1") (pinfunction "BOOT_1") (pintype "output"))
    )
    (net (code "31") (name "Net-(U6-COMP)") (class "Default")
      (node (ref "C44") (pin "1") (pinfunction "1_1") (pintype "passive"))
      (node (ref "R48") (pin "2") (pinfunction "2_2") (pintype "passive"))
      (node (ref "U6") (pin "6") (pinfunction "COMP_6") (pintype "output"))
    )
    (net (code "32") (name "Net-(U6-EN)") (class "Default")
      (node (ref "SB3") (pin "2") (pinfunction "2_2") (pintype "passive"))
      (node (ref "U6") (pin "3") (pinfunction "EN_3") (pintype "input"))
    )
    (net (code "33") (name "Net-(U6-SS)") (class "Default")
      (node (ref "C46") (pin "1") (pinfunction "1_1") (pintype "passive"))
      (node (ref "U6") (pin "4") (pinfunction "SS_4") (pintype "input"))
    )
    (net (code "34") (name "Net-(U6-VSENSE)") (class "Default")
      (node (ref "R46") (pin "1") (pinfunction "1_1") (pintype "passive"))
      (node (ref "R50") (pin "2") (pinfunction "2_2") (pintype "passive"))
      (node (ref "U6") (pin "5") (pinfunction "VSENSE_5") (pintype "input"))
    )
    (net (code "35") (name "Net-(U7-BOOT)") (class "Default")
      (node (ref "C41") (pin "1") (pinfunction "1_1") (pintype "passive"))
      (node (ref "U7") (pin "1") (pinfunction "BOOT_1") (pintype "output"))
    )
    (net (code "36") (name "Net-(U7-COMP)") (class "Default")
      (node (ref "C47") (pin "1") (pinfunction "1_1") (pintype "passive"))
      (node (ref "R49") (pin "2") (pinfunction "2_2") (pintype "passive"))
      (node (ref "U7") (pin "6") (pinfunction "COMP_6") (pintype "output"))
    )
    (net (code "37") (name "Net-(U7-EN)") (class "Default")
      (node (ref "SB4") (pin "2") (pinfunction "2_2") (pintype "passive"))
      (node (ref "U7") (pin "3") (pinfunction "EN_3") (pintype "input"))
    )
    (net (code "38") (name "Net-(U7-SS)") (class "Default")
      (node (ref "C49") (pin "1") (pinfunction "1_1") (pintype "passive"))
      (node (ref "U7") (pin "4") (pinfunction "SS_4") (pintype "input"))
    )
    (net (code "39") (name "Net-(U7-VSENSE)") (class "Default")
      (node (ref "R47") (pin "1") (pinfunction "1_1") (pintype "passive"))
      (node (ref "R51") (pin "2") (pinfunction "2_2") (pintype "passive"))
      (node (ref "U7") (pin "5") (pinfunction "VSENSE_5") (pintype "input"))
    )
    (net (code "40") (name "VBUS_PD") (class "Default")
      (node (ref "C31") (pin "2") (pinfunction "2_2") (pintype "passive"))
      (node (ref "C32") (pin "1") (pinfunction "1_1") (pintype "passive"))
      (node (ref "C33") (pin "1") (pinfunction "1_1") (pintype "passive"))
      (node (ref "C38") (pin "2") (pinfunction "2_2") (pintype "passive"))
      (node (ref "C40") (pin "2") (pinfunction "2_2") (pintype "passive"))
      (node (ref "D12") (pin "K") (pinfunction "K_K") (pintype "passive"))
      (node (ref "R42") (pin "2") (pinfunction "2_2") (pintype "passive"))
      (node (ref "U4") (pin "2") (pinfunction "IN2_2") (pintype "input"))
      (node (ref "U6") (pin "2") (pinfunction "VIN_2") (pintype "power_in"))
      (node (ref "U7") (pin "2") (pinfunction "VIN_2") (pintype "power_in"))
    )
  )
)
